# Sheet2.net
KiCad netlist of a schematic drawn in Altium Designer
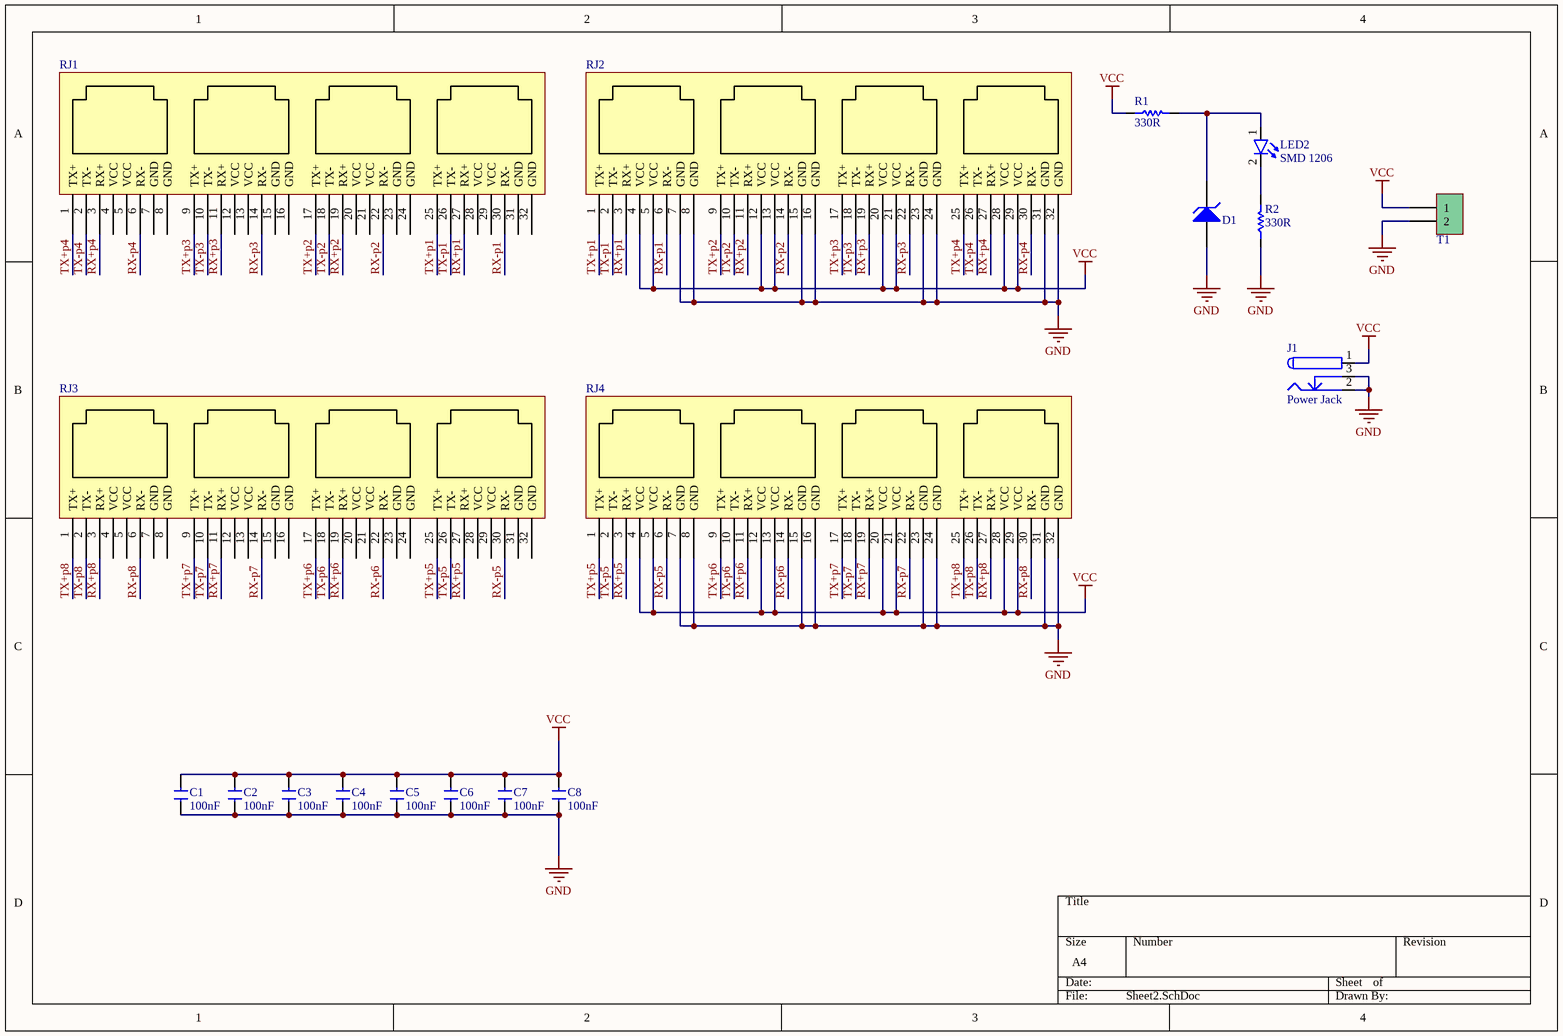
[diagram p0: Sheet2.SchDoc]

(export (version "E")
  (design (tool "Eeschema 10.0.6"))
  (components
    (comp (ref "C1")
      (value "Capacitor SMD")
      (footprint "1206 Capacitor")
      (fields (field (name "ALTIUM_UNNAMED_1") "100nF"))
      (libsource (lib "ZetaBoard_Lib") (part "Capacitor SMD"))
    )
    (comp (ref "C2")
      (value "Capacitor SMD")
      (footprint "1206 Capacitor")
      (fields (field (name "ALTIUM_UNNAMED_1") "100nF"))
      (libsource (lib "ZetaBoard_Lib") (part "Capacitor SMD"))
    )
    (comp (ref "C3")
      (value "Capacitor SMD")
      (footprint "1206 Capacitor")
      (fields (field (name "ALTIUM_UNNAMED_1") "100nF"))
      (libsource (lib "ZetaBoard_Lib") (part "Capacitor SMD"))
    )
    (comp (ref "C4")
      (value "Capacitor SMD")
      (footprint "1206 Capacitor")
      (fields (field (name "ALTIUM_UNNAMED_1") "100nF"))
      (libsource (lib "ZetaBoard_Lib") (part "Capacitor SMD"))
    )
    (comp (ref "C5")
      (value "Capacitor SMD")
      (footprint "1206 Capacitor")
      (fields (field (name "ALTIUM_UNNAMED_1") "100nF"))
      (libsource (lib "ZetaBoard_Lib") (part "Capacitor SMD"))
    )
    (comp (ref "C6")
      (value "Capacitor SMD")
      (footprint "1206 Capacitor")
      (fields (field (name "ALTIUM_UNNAMED_1") "100nF"))
      (libsource (lib "ZetaBoard_Lib") (part "Capacitor SMD"))
    )
    (comp (ref "C7")
      (value "Capacitor SMD")
      (footprint "1206 Capacitor")
      (fields (field (name "ALTIUM_UNNAMED_1") "100nF"))
      (libsource (lib "ZetaBoard_Lib") (part "Capacitor SMD"))
    )
    (comp (ref "C8")
      (value "Capacitor SMD")
      (footprint "1206 Capacitor")
      (fields (field (name "ALTIUM_UNNAMED_1") "100nF"))
      (libsource (lib "ZetaBoard_Lib") (part "Capacitor SMD"))
    )
    (comp (ref "D1")
      (value "Diode Zener")
      (footprint "Diode 1W")
      (description "Zener Diode")
      (fields (field (name "VOLTAGE") "12V") (field (name "DESIGNER") "Saeid Jorablo"))
      (libsource (lib "Electrovolt Lib") (part "Diode Zener"))
    )
    (comp (ref "J1")
      (value "Power Jack")
      (footprint "Power Jack")
      (fields (field (name "DESIGNER") "Saeid Jorablo"))
      (libsource (lib "Electrovolt Lib") (part "Power Jack"))
    )
    (comp (ref "LED2")
      (value "Red")
      (footprint "LED-5mm")
      (description "LED")
      (fields (field (name "SIZE") "SMD 1206") (field (name "DESIGNER") "Saeid Jorablo"))
      (libsource (lib "Electrovolt Lib") (part "LED"))
    )
    (comp (ref "R1")
      (value "330R")
      (footprint "Res-(1/2)")
      (description "Resistor")
      (fields (field (name "TOLERANCE") "5%") (field (name "POWER") "1/8 W"))
      (libsource (lib "Electrovolt Lib") (part "Resistor"))
    )
    (comp (ref "R2")
      (value "330R")
      (footprint "RES 1206 (3216X08L)")
      (description "Resistor")
      (fields (field (name "TOLERANCE") "5%") (field (name "POWER") "1/8 W"))
      (libsource (lib "Electrovolt Lib") (part "Resistor"))
    )
    (comp (ref "RJ1") (value "~") (footprint "rj45-w57-4") (libsource (lib "Schlib1") (part "RJ45-w57-4")))
    (comp (ref "RJ2") (value "~") (footprint "rj45-w57-4") (libsource (lib "Schlib1") (part "RJ45-w57-4")))
    (comp (ref "RJ3") (value "~") (footprint "rj45-w57-4") (libsource (lib "Schlib1") (part "RJ45-w57-4")))
    (comp (ref "RJ4") (value "~") (footprint "rj45-w57-4") (libsource (lib "Schlib1") (part "RJ45-w57-4")))
    (comp (ref "T1")
      (value "Phoenix terminal")
      (footprint "phoenix terminal 2")
      (description "Terminal 2 Pin")
      (fields (field (name "DESIGNER") "Seyed Mohsen Ghasemain") (field (name "E-MAIL") "picpars@gmail.com"))
      (libsource (lib "usefully_Library") (part "Phoenix terminal 2"))
    )
  )
  (nets
    (net (code "1") (name "/RX+p1") (class "Default")
      (node (ref "RJ1") (pin "27") (pinfunction "RX+_27") (pintype "passive"))
      (node (ref "RJ2") (pin "3") (pinfunction "RX+_3") (pintype "passive"))
    )
    (net (code "2") (name "/RX+p2") (class "Default")
      (node (ref "RJ1") (pin "19") (pinfunction "RX+_19") (pintype "passive"))
      (node (ref "RJ2") (pin "11") (pinfunction "RX+_11") (pintype "passive"))
    )
    (net (code "3") (name "/RX+p3") (class "Default")
      (node (ref "RJ1") (pin "11") (pinfunction "RX+_11") (pintype "passive"))
      (node (ref "RJ2") (pin "19") (pinfunction "RX+_19") (pintype "passive"))
    )
    (net (code "4") (name "/RX+p4") (class "Default")
      (node (ref "RJ1") (pin "3") (pinfunction "RX+_3") (pintype "passive"))
      (node (ref "RJ2") (pin "27") (pinfunction "RX+_27") (pintype "passive"))
    )
    (net (code "5") (name "/RX+p5") (class "Default")
      (node (ref "RJ3") (pin "27") (pinfunction "RX+_27") (pintype "passive"))
      (node (ref "RJ4") (pin "3") (pinfunction "RX+_3") (pintype "passive"))
    )
    (net (code "6") (name "/RX+p6") (class "Default")
      (node (ref "RJ3") (pin "19") (pinfunction "RX+_19") (pintype "passive"))
      (node (ref "RJ4") (pin "11") (pinfunction "RX+_11") (pintype "passive"))
    )
    (net (code "7") (name "/RX+p7") (class "Default")
      (node (ref "RJ3") (pin "11") (pinfunction "RX+_11") (pintype "passive"))
      (node (ref "RJ4") (pin "19") (pinfunction "RX+_19") (pintype "passive"))
    )
    (net (code "8") (name "/RX+p8") (class "Default")
      (node (ref "RJ3") (pin "3") (pinfunction "RX+_3") (pintype "passive"))
      (node (ref "RJ4") (pin "27") (pinfunction "RX+_27") (pintype "passive"))
    )
    (net (code "9") (name "/RX-p1") (class "Default")
      (node (ref "RJ1") (pin "30") (pinfunction "RX-_30") (pintype "passive"))
      (node (ref "RJ2") (pin "6") (pinfunction "RX-_6") (pintype "passive"))
    )
    (net (code "10") (name "/RX-p2") (class "Default")
      (node (ref "RJ1") (pin "22") (pinfunction "RX-_22") (pintype "passive"))
      (node (ref "RJ2") (pin "14") (pinfunction "RX-_14") (pintype "passive"))
    )
    (net (code "11") (name "/RX-p3") (class "Default")
      (node (ref "RJ1") (pin "14") (pinfunction "RX-_14") (pintype "passive"))
      (node (ref "RJ2") (pin "22") (pinfunction "RX-_22") (pintype "passive"))
    )
    (net (code "12") (name "/RX-p4") (class "Default")
      (node (ref "RJ1") (pin "6") (pinfunction "RX-_6") (pintype "passive"))
      (node (ref "RJ2") (pin "30") (pinfunction "RX-_30") (pintype "passive"))
    )
    (net (code "13") (name "/RX-p5") (class "Default")
      (node (ref "RJ3") (pin "30") (pinfunction "RX-_30") (pintype "passive"))
      (node (ref "RJ4") (pin "6") (pinfunction "RX-_6") (pintype "passive"))
    )
    (net (code "14") (name "/RX-p6") (class "Default")
      (node (ref "RJ3") (pin "22") (pinfunction "RX-_22") (pintype "passive"))
      (node (ref "RJ4") (pin "14") (pinfunction "RX-_14") (pintype "passive"))
    )
    (net (code "15") (name "/RX-p7") (class "Default")
      (node (ref "RJ3") (pin "14") (pinfunction "RX-_14") (pintype "passive"))
      (node (ref "RJ4") (pin "22") (pinfunction "RX-_22") (pintype "passive"))
    )
    (net (code "16") (name "/RX-p8") (class "Default")
      (node (ref "RJ3") (pin "6") (pinfunction "RX-_6") (pintype "passive"))
      (node (ref "RJ4") (pin "30") (pinfunction "RX-_30") (pintype "passive"))
    )
    (net (code "17") (name "/TX+p1") (class "Default")
      (node (ref "RJ1") (pin "25") (pinfunction "TX+_25") (pintype "passive"))
      (node (ref "RJ2") (pin "1") (pinfunction "TX+_1") (pintype "passive"))
    )
    (net (code "18") (name "/TX+p2") (class "Default")
      (node (ref "RJ1") (pin "17") (pinfunction "TX+_17") (pintype "passive"))
      (node (ref "RJ2") (pin "9") (pinfunction "TX+_9") (pintype "passive"))
    )
    (net (code "19") (name "/TX+p3") (class "Default")
      (node (ref "RJ1") (pin "9") (pinfunction "TX+_9") (pintype "passive"))
      (node (ref "RJ2") (pin "17") (pinfunction "TX+_17") (pintype "passive"))
    )
    (net (code "20") (name "/TX+p4") (class "Default")
      (node (ref "RJ1") (pin "1") (pinfunction "TX+_1") (pintype "passive"))
      (node (ref "RJ2") (pin "25") (pinfunction "TX+_25") (pintype "passive"))
    )
    (net (code "21") (name "/TX+p5") (class "Default")
      (node (ref "RJ3") (pin "25") (pinfunction "TX+_25") (pintype "passive"))
      (node (ref "RJ4") (pin "1") (pinfunction "TX+_1") (pintype "passive"))
    )
    (net (code "22") (name "/TX+p6") (class "Default")
      (node (ref "RJ3") (pin "17") (pinfunction "TX+_17") (pintype "passive"))
      (node (ref "RJ4") (pin "9") (pinfunction "TX+_9") (pintype "passive"))
    )
    (net (code "23") (name "/TX+p7") (class "Default")
      (node (ref "RJ3") (pin "9") (pinfunction "TX+_9") (pintype "passive"))
      (node (ref "RJ4") (pin "17") (pinfunction "TX+_17") (pintype "passive"))
    )
    (net (code "24") (name "/TX+p8") (class "Default")
      (node (ref "RJ3") (pin "1") (pinfunction "TX+_1") (pintype "passive"))
      (node (ref "RJ4") (pin "25") (pinfunction "TX+_25") (pintype "passive"))
    )
    (net (code "25") (name "/TX-p1") (class "Default")
      (node (ref "RJ1") (pin "26") (pinfunction "TX-_26") (pintype "passive"))
      (node (ref "RJ2") (pin "2") (pinfunction "TX-_2") (pintype "passive"))
    )
    (net (code "26") (name "/TX-p2") (class "Default")
      (node (ref "RJ1") (pin "18") (pinfunction "TX-_18") (pintype "passive"))
      (node (ref "RJ2") (pin "10") (pinfunction "TX-_10") (pintype "passive"))
    )
    (net (code "27") (name "/TX-p3") (class "Default")
      (node (ref "RJ1") (pin "10") (pinfunction "TX-_10") (pintype "passive"))
      (node (ref "RJ2") (pin "18") (pinfunction "TX-_18") (pintype "passive"))
    )
    (net (code "28") (name "/TX-p4") (class "Default")
      (node (ref "RJ1") (pin "2") (pinfunction "TX-_2") (pintype "passive"))
      (node (ref "RJ2") (pin "26") (pinfunction "TX-_26") (pintype "passive"))
    )
    (net (code "29") (name "/TX-p5") (class "Default")
      (node (ref "RJ3") (pin "26") (pinfunction "TX-_26") (pintype "passive"))
      (node (ref "RJ4") (pin "2") (pinfunction "TX-_2") (pintype "passive"))
    )
    (net (code "30") (name "/TX-p6") (class "Default")
      (node (ref "RJ3") (pin "18") (pinfunction "TX-_18") (pintype "passive"))
      (node (ref "RJ4") (pin "10") (pinfunction "TX-_10") (pintype "passive"))
    )
    (net (code "31") (name "/TX-p7") (class "Default")
      (node (ref "RJ3") (pin "10") (pinfunction "TX-_10") (pintype "passive"))
      (node (ref "RJ4") (pin "18") (pinfunction "TX-_18") (pintype "passive"))
    )
    (net (code "32") (name "/TX-p8") (class "Default")
      (node (ref "RJ3") (pin "2") (pinfunction "TX-_2") (pintype "passive"))
      (node (ref "RJ4") (pin "26") (pinfunction "TX-_26") (pintype "passive"))
    )
    (net (code "33") (name "GND") (class "Default")
      (node (ref "C1") (pin "1") (pintype "passive"))
      (node (ref "C2") (pin "1") (pintype "passive"))
      (node (ref "C3") (pin "1") (pintype "passive"))
      (node (ref "C4") (pin "1") (pintype "passive"))
      (node (ref "C5") (pin "1") (pintype "passive"))
      (node (ref "C6") (pin "1") (pintype "passive"))
      (node (ref "C7") (pin "1") (pintype "passive"))
      (node (ref "C8") (pin "1") (pintype "passive"))
      (node (ref "D1") (pin "1") (pinfunction "A_1") (pintype "passive"))
      (node (ref "J1") (pin "2") (pinfunction "2_2") (pintype "power_in"))
      (node (ref "J1") (pin "3") (pinfunction "3_3") (pintype "power_in"))
      (node (ref "R2") (pin "1") (pinfunction "1_1") (pintype "passive"))
      (node (ref "RJ2") (pin "15") (pinfunction "GND_15") (pintype "passive"))
      (node (ref "RJ2") (pin "16") (pinfunction "GND_16") (pintype "passive"))
      (node (ref "RJ2") (pin "23") (pinfunction "GND_23") (pintype "passive"))
      (node (ref "RJ2") (pin "24") (pinfunction "GND_24") (pintype "passive"))
      (node (ref "RJ2") (pin "31") (pinfunction "GND_31") (pintype "passive"))
      (node (ref "RJ2") (pin "32") (pinfunction "GND_32") (pintype "passive"))
      (node (ref "RJ2") (pin "7") (pinfunction "GND_7") (pintype "passive"))
      (node (ref "RJ2") (pin "8") (pinfunction "GND_8") (pintype "passive"))
      (node (ref "RJ4") (pin "15") (pinfunction "GND_15") (pintype "passive"))
      (node (ref "RJ4") (pin "16") (pinfunction "GND_16") (pintype "passive"))
      (node (ref "RJ4") (pin "23") (pinfunction "GND_23") (pintype "passive"))
      (node (ref "RJ4") (pin "24") (pinfunction "GND_24") (pintype "passive"))
      (node (ref "RJ4") (pin "31") (pinfunction "GND_31") (pintype "passive"))
      (node (ref "RJ4") (pin "32") (pinfunction "GND_32") (pintype "passive"))
      (node (ref "RJ4") (pin "7") (pinfunction "GND_7") (pintype "passive"))
      (node (ref "RJ4") (pin "8") (pinfunction "GND_8") (pintype "passive"))
      (node (ref "T1") (pin "2") (pinfunction "2_2") (pintype "passive"))
    )
    (net (code "34") (name "Net-(D1-K)") (class "Default")
      (node (ref "D1") (pin "2") (pinfunction "K_2") (pintype "passive"))
      (node (ref "LED2") (pin "1") (pinfunction "A_1") (pintype "passive"))
      (node (ref "R1") (pin "2") (pinfunction "2_2") (pintype "passive"))
    )
    (net (code "35") (name "Net-(LED2-K)") (class "Default")
      (node (ref "LED2") (pin "2") (pinfunction "K_2") (pintype "passive"))
      (node (ref "R2") (pin "2") (pinfunction "2_2") (pintype "passive"))
    )
    (net (code "36") (name "VCC") (class "Default")
      (node (ref "C1") (pin "2") (pintype "passive"))
      (node (ref "C2") (pin "2") (pintype "passive"))
      (node (ref "C3") (pin "2") (pintype "passive"))
      (node (ref "C4") (pin "2") (pintype "passive"))
      (node (ref "C5") (pin "2") (pintype "passive"))
      (node (ref "C6") (pin "2") (pintype "passive"))
      (node (ref "C7") (pin "2") (pintype "passive"))
      (node (ref "C8") (pin "2") (pintype "passive"))
      (node (ref "J1") (pin "1") (pinfunction "1_1") (pintype "power_in"))
      (node (ref "R1") (pin "1") (pinfunction "1_1") (pintype "passive"))
      (node (ref "RJ2") (pin "12") (pinfunction "VCC_12") (pintype "passive"))
      (node (ref "RJ2") (pin "13") (pinfunction "VCC_13") (pintype "passive"))
      (node (ref "RJ2") (pin "20") (pinfunction "VCC_20") (pintype "passive"))
      (node (ref "RJ2") (pin "21") (pinfunction "VCC_21") (pintype "passive"))
      (node (ref "RJ2") (pin "28") (pinfunction "VCC_28") (pintype "passive"))
      (node (ref "RJ2") (pin "29") (pinfunction "VCC_29") (pintype "passive"))
      (node (ref "RJ2") (pin "4") (pinfunction "VCC_4") (pintype "passive"))
      (node (ref "RJ2") (pin "5") (pinfunction "VCC_5") (pintype "passive"))
      (node (ref "RJ4") (pin "12") (pinfunction "VCC_12") (pintype "passive"))
      (node (ref "RJ4") (pin "13") (pinfunction "VCC_13") (pintype "passive"))
      (node (ref "RJ4") (pin "20") (pinfunction "VCC_20") (pintype "passive"))
      (node (ref "RJ4") (pin "21") (pinfunction "VCC_21") (pintype "passive"))
      (node (ref "RJ4") (pin "28") (pinfunction "VCC_28") (pintype "passive"))
      (node (ref "RJ4") (pin "29") (pinfunction "VCC_29") (pintype "passive"))
      (node (ref "RJ4") (pin "4") (pinfunction "VCC_4") (pintype "passive"))
      (node (ref "RJ4") (pin "5") (pinfunction "VCC_5") (pintype "passive"))
      (node (ref "T1") (pin "1") (pinfunction "1_1") (pintype "passive"))
    )
    (net (code "37") (name "unconnected-(RJ1-GND-Pad7)") (class "Default")
      (node (ref "RJ1") (pin "7") (pinfunction "GND_7") (pintype "passive"))
    )
    (net (code "38") (name "unconnected-(RJ1-GND-Pad8)") (class "Default")
      (node (ref "RJ1") (pin "8") (pinfunction "GND_8") (pintype "passive"))
    )
    (net (code "39") (name "unconnected-(RJ1-GND-Pad15)") (class "Default")
      (node (ref "RJ1") (pin "15") (pinfunction "GND_15") (pintype "passive"))
    )
    (net (code "40") (name "unconnected-(RJ1-GND-Pad16)") (class "Default")
      (node (ref "RJ1") (pin "16") (pinfunction "GND_16") (pintype "passive"))
    )
    (net (code "41") (name "unconnected-(RJ1-GND-Pad23)") (class "Default")
      (node (ref "RJ1") (pin "23") (pinfunction "GND_23") (pintype "passive"))
    )
    (net (code "42") (name "unconnected-(RJ1-GND-Pad24)") (class "Default")
      (node (ref "RJ1") (pin "24") (pinfunction "GND_24") (pintype "passive"))
    )
    (net (code "43") (name "unconnected-(RJ1-GND-Pad31)") (class "Default")
      (node (ref "RJ1") (pin "31") (pinfunction "GND_31") (pintype "passive"))
    )
    (net (code "44") (name "unconnected-(RJ1-GND-Pad32)") (class "Default")
      (node (ref "RJ1") (pin "32") (pinfunction "GND_32") (pintype "passive"))
    )
    (net (code "45") (name "unconnected-(RJ1-VCC-Pad4)") (class "Default")
      (node (ref "RJ1") (pin "4") (pinfunction "VCC_4") (pintype "passive"))
    )
    (net (code "46") (name "unconnected-(RJ1-VCC-Pad5)") (class "Default")
      (node (ref "RJ1") (pin "5") (pinfunction "VCC_5") (pintype "passive"))
    )
    (net (code "47") (name "unconnected-(RJ1-VCC-Pad12)") (class "Default")
      (node (ref "RJ1") (pin "12") (pinfunction "VCC_12") (pintype "passive"))
    )
    (net (code "48") (name "unconnected-(RJ1-VCC-Pad13)") (class "Default")
      (node (ref "RJ1") (pin "13") (pinfunction "VCC_13") (pintype "passive"))
    )
    (net (code "49") (name "unconnected-(RJ1-VCC-Pad20)") (class "Default")
      (node (ref "RJ1") (pin "20") (pinfunction "VCC_20") (pintype "passive"))
    )
    (net (code "50") (name "unconnected-(RJ1-VCC-Pad21)") (class "Default")
      (node (ref "RJ1") (pin "21") (pinfunction "VCC_21") (pintype "passive"))
    )
    (net (code "51") (name "unconnected-(RJ1-VCC-Pad28)") (class "Default")
      (node (ref "RJ1") (pin "28") (pinfunction "VCC_28") (pintype "passive"))
    )
    (net (code "52") (name "unconnected-(RJ1-VCC-Pad29)") (class "Default")
      (node (ref "RJ1") (pin "29") (pinfunction "VCC_29") (pintype "passive"))
    )
    (net (code "53") (name "unconnected-(RJ3-GND-Pad7)") (class "Default")
      (node (ref "RJ3") (pin "7") (pinfunction "GND_7") (pintype "passive"))
    )
    (net (code "54") (name "unconnected-(RJ3-GND-Pad8)") (class "Default")
      (node (ref "RJ3") (pin "8") (pinfunction "GND_8") (pintype "passive"))
    )
    (net (code "55") (name "unconnected-(RJ3-GND-Pad15)") (class "Default")
      (node (ref "RJ3") (pin "15") (pinfunction "GND_15") (pintype "passive"))
    )
    (net (code "56") (name "unconnected-(RJ3-GND-Pad16)") (class "Default")
      (node (ref "RJ3") (pin "16") (pinfunction "GND_16") (pintype "passive"))
    )
    (net (code "57") (name "unconnected-(RJ3-GND-Pad23)") (class "Default")
      (node (ref "RJ3") (pin "23") (pinfunction "GND_23") (pintype "passive"))
    )
    (net (code "58") (name "unconnected-(RJ3-GND-Pad24)") (class "Default")
      (node (ref "RJ3") (pin "24") (pinfunction "GND_24") (pintype "passive"))
    )
    (net (code "59") (name "unconnected-(RJ3-GND-Pad31)") (class "Default")
      (node (ref "RJ3") (pin "31") (pinfunction "GND_31") (pintype "passive"))
    )
    (net (code "60") (name "unconnected-(RJ3-GND-Pad32)") (class "Default")
      (node (ref "RJ3") (pin "32") (pinfunction "GND_32") (pintype "passive"))
    )
    (net (code "61") (name "unconnected-(RJ3-VCC-Pad4)") (class "Default")
      (node (ref "RJ3") (pin "4") (pinfunction "VCC_4") (pintype "passive"))
    )
    (net (code "62") (name "unconnected-(RJ3-VCC-Pad5)") (class "Default")
      (node (ref "RJ3") (pin "5") (pinfunction "VCC_5") (pintype "passive"))
    )
    (net (code "63") (name "unconnected-(RJ3-VCC-Pad12)") (class "Default")
      (node (ref "RJ3") (pin "12") (pinfunction "VCC_12") (pintype "passive"))
    )
    (net (code "64") (name "unconnected-(RJ3-VCC-Pad13)") (class "Default")
      (node (ref "RJ3") (pin "13") (pinfunction "VCC_13") (pintype "passive"))
    )
    (net (code "65") (name "unconnected-(RJ3-VCC-Pad20)") (class "Default")
      (node (ref "RJ3") (pin "20") (pinfunction "VCC_20") (pintype "passive"))
    )
    (net (code "66") (name "unconnected-(RJ3-VCC-Pad21)") (class "Default")
      (node (ref "RJ3") (pin "21") (pinfunction "VCC_21") (pintype "passive"))
    )
    (net (code "67") (name "unconnected-(RJ3-VCC-Pad28)") (class "Default")
      (node (ref "RJ3") (pin "28") (pinfunction "VCC_28") (pintype "passive"))
    )
    (net (code "68") (name "unconnected-(RJ3-VCC-Pad29)") (class "Default")
      (node (ref "RJ3") (pin "29") (pinfunction "VCC_29") (pintype "passive"))
    )
  )
)
